# Tubes.net
KiCad netlist of a schematic drawn in EAGLE
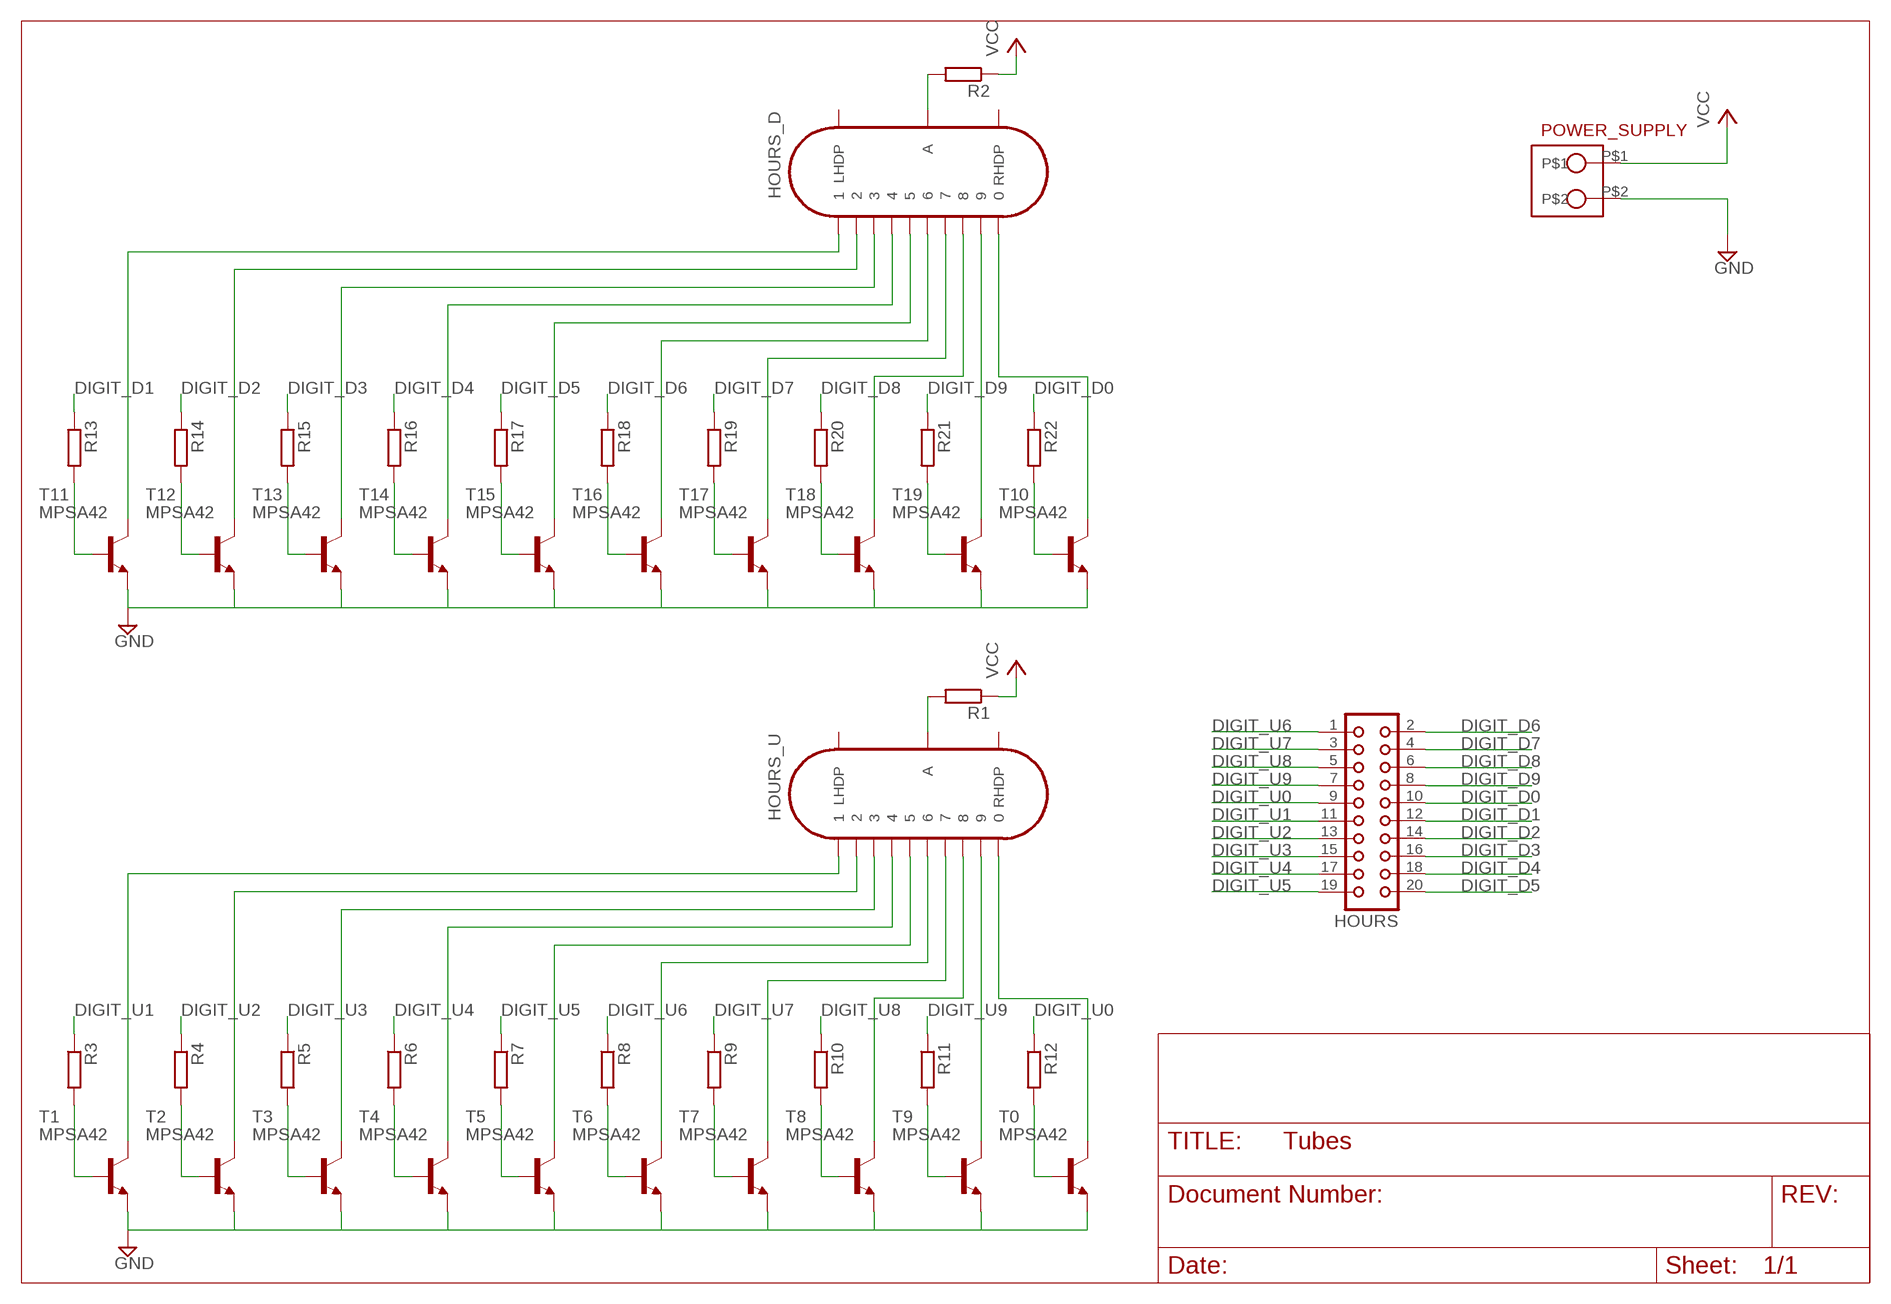
[diagram p0: schematic, sheet 1]

(export (version "E")
  (design (tool "Eeschema 10.0.6"))
  (components
    (comp (ref "HOURS")
      (value "CON20")
      (footprint "eagle-import:CON20")
      (libsource (lib "eagle-import") (part "CON20"))
    )
    (comp (ref "HOURS_D")
      (value "IN-14")
      (footprint "eagle-import:IN-14")
      (libsource (lib "eagle-import") (part "IN-14"))
    )
    (comp (ref "HOURS_U")
      (value "IN-14")
      (footprint "eagle-import:IN-14")
      (libsource (lib "eagle-import") (part "IN-14"))
    )
    (comp (ref "POWER_SUPPLY")
      (value "CON_2_SIL")
      (footprint "eagle-import:SIL_2_0.2INCH")
      (libsource (lib "eagle-import") (part "CON_2_SIL"))
    )
    (comp (ref "R1")
      (value "R-EU_0207/10")
      (footprint "eagle-import:0207_10")
      (libsource (lib "eagle-import") (part "R-EU_0207/10"))
    )
    (comp (ref "R2")
      (value "R-EU_0207/10")
      (footprint "eagle-import:0207_10")
      (libsource (lib "eagle-import") (part "R-EU_0207/10"))
    )
    (comp (ref "R3")
      (value "R-EU_0207/10")
      (footprint "eagle-import:0207_10")
      (libsource (lib "eagle-import") (part "R-EU_0207/10"))
    )
    (comp (ref "R4")
      (value "R-EU_0207/10")
      (footprint "eagle-import:0207_10")
      (libsource (lib "eagle-import") (part "R-EU_0207/10"))
    )
    (comp (ref "R5")
      (value "R-EU_0207/10")
      (footprint "eagle-import:0207_10")
      (libsource (lib "eagle-import") (part "R-EU_0207/10"))
    )
    (comp (ref "R6")
      (value "R-EU_0207/10")
      (footprint "eagle-import:0207_10")
      (libsource (lib "eagle-import") (part "R-EU_0207/10"))
    )
    (comp (ref "R7")
      (value "R-EU_0207/10")
      (footprint "eagle-import:0207_10")
      (libsource (lib "eagle-import") (part "R-EU_0207/10"))
    )
    (comp (ref "R8")
      (value "R-EU_0207/10")
      (footprint "eagle-import:0207_10")
      (libsource (lib "eagle-import") (part "R-EU_0207/10"))
    )
    (comp (ref "R9")
      (value "R-EU_0207/10")
      (footprint "eagle-import:0207_10")
      (libsource (lib "eagle-import") (part "R-EU_0207/10"))
    )
    (comp (ref "R10")
      (value "R-EU_0207/10")
      (footprint "eagle-import:0207_10")
      (libsource (lib "eagle-import") (part "R-EU_0207/10"))
    )
    (comp (ref "R11")
      (value "R-EU_0207/10")
      (footprint "eagle-import:0207_10")
      (libsource (lib "eagle-import") (part "R-EU_0207/10"))
    )
    (comp (ref "R12")
      (value "R-EU_0207/10")
      (footprint "eagle-import:0207_10")
      (libsource (lib "eagle-import") (part "R-EU_0207/10"))
    )
    (comp (ref "R13")
      (value "R-EU_0207/10")
      (footprint "eagle-import:0207_10")
      (libsource (lib "eagle-import") (part "R-EU_0207/10"))
    )
    (comp (ref "R14")
      (value "R-EU_0207/10")
      (footprint "eagle-import:0207_10")
      (libsource (lib "eagle-import") (part "R-EU_0207/10"))
    )
    (comp (ref "R15")
      (value "R-EU_0207/10")
      (footprint "eagle-import:0207_10")
      (libsource (lib "eagle-import") (part "R-EU_0207/10"))
    )
    (comp (ref "R16")
      (value "R-EU_0207/10")
      (footprint "eagle-import:0207_10")
      (libsource (lib "eagle-import") (part "R-EU_0207/10"))
    )
    (comp (ref "R17")
      (value "R-EU_0207/10")
      (footprint "eagle-import:0207_10")
      (libsource (lib "eagle-import") (part "R-EU_0207/10"))
    )
    (comp (ref "R18")
      (value "R-EU_0207/10")
      (footprint "eagle-import:0207_10")
      (libsource (lib "eagle-import") (part "R-EU_0207/10"))
    )
    (comp (ref "R19")
      (value "R-EU_0207/10")
      (footprint "eagle-import:0207_10")
      (libsource (lib "eagle-import") (part "R-EU_0207/10"))
    )
    (comp (ref "R20")
      (value "R-EU_0207/10")
      (footprint "eagle-import:0207_10")
      (libsource (lib "eagle-import") (part "R-EU_0207/10"))
    )
    (comp (ref "R21")
      (value "R-EU_0207/10")
      (footprint "eagle-import:0207_10")
      (libsource (lib "eagle-import") (part "R-EU_0207/10"))
    )
    (comp (ref "R22")
      (value "R-EU_0207/10")
      (footprint "eagle-import:0207_10")
      (libsource (lib "eagle-import") (part "R-EU_0207/10"))
    )
    (comp (ref "T0")
      (value "MPSA42")
      (footprint "eagle-import:TO92")
      (libsource (lib "eagle-import") (part "MPSA42"))
    )
    (comp (ref "T1")
      (value "MPSA42")
      (footprint "eagle-import:TO92")
      (libsource (lib "eagle-import") (part "MPSA42"))
    )
    (comp (ref "T2")
      (value "MPSA42")
      (footprint "eagle-import:TO92")
      (libsource (lib "eagle-import") (part "MPSA42"))
    )
    (comp (ref "T3")
      (value "MPSA42")
      (footprint "eagle-import:TO92")
      (libsource (lib "eagle-import") (part "MPSA42"))
    )
    (comp (ref "T4")
      (value "MPSA42")
      (footprint "eagle-import:TO92")
      (libsource (lib "eagle-import") (part "MPSA42"))
    )
    (comp (ref "T5")
      (value "MPSA42")
      (footprint "eagle-import:TO92")
      (libsource (lib "eagle-import") (part "MPSA42"))
    )
    (comp (ref "T6")
      (value "MPSA42")
      (footprint "eagle-import:TO92")
      (libsource (lib "eagle-import") (part "MPSA42"))
    )
    (comp (ref "T7")
      (value "MPSA42")
      (footprint "eagle-import:TO92")
      (libsource (lib "eagle-import") (part "MPSA42"))
    )
    (comp (ref "T8")
      (value "MPSA42")
      (footprint "eagle-import:TO92")
      (libsource (lib "eagle-import") (part "MPSA42"))
    )
    (comp (ref "T9")
      (value "MPSA42")
      (footprint "eagle-import:TO92")
      (libsource (lib "eagle-import") (part "MPSA42"))
    )
    (comp (ref "T10")
      (value "MPSA42")
      (footprint "eagle-import:TO92")
      (libsource (lib "eagle-import") (part "MPSA42"))
    )
    (comp (ref "T11")
      (value "MPSA42")
      (footprint "eagle-import:TO92")
      (libsource (lib "eagle-import") (part "MPSA42"))
    )
    (comp (ref "T12")
      (value "MPSA42")
      (footprint "eagle-import:TO92")
      (libsource (lib "eagle-import") (part "MPSA42"))
    )
    (comp (ref "T13")
      (value "MPSA42")
      (footprint "eagle-import:TO92")
      (libsource (lib "eagle-import") (part "MPSA42"))
    )
    (comp (ref "T14")
      (value "MPSA42")
      (footprint "eagle-import:TO92")
      (libsource (lib "eagle-import") (part "MPSA42"))
    )
    (comp (ref "T15")
      (value "MPSA42")
      (footprint "eagle-import:TO92")
      (libsource (lib "eagle-import") (part "MPSA42"))
    )
    (comp (ref "T16")
      (value "MPSA42")
      (footprint "eagle-import:TO92")
      (libsource (lib "eagle-import") (part "MPSA42"))
    )
    (comp (ref "T17")
      (value "MPSA42")
      (footprint "eagle-import:TO92")
      (libsource (lib "eagle-import") (part "MPSA42"))
    )
    (comp (ref "T18")
      (value "MPSA42")
      (footprint "eagle-import:TO92")
      (libsource (lib "eagle-import") (part "MPSA42"))
    )
    (comp (ref "T19")
      (value "MPSA42")
      (footprint "eagle-import:TO92")
      (libsource (lib "eagle-import") (part "MPSA42"))
    )
  )
  (nets
    (net (code "1") (name "/DIGIT_D0") (class "Default")
      (node (ref "HOURS") (pin "10") (pinfunction "10_10") (pintype "passive"))
      (node (ref "R22") (pin "1") (pinfunction "1_1") (pintype "passive"))
    )
    (net (code "2") (name "/DIGIT_D1") (class "Default")
      (node (ref "HOURS") (pin "12") (pinfunction "12_12") (pintype "passive"))
      (node (ref "R13") (pin "1") (pinfunction "1_1") (pintype "passive"))
    )
    (net (code "3") (name "/DIGIT_D2") (class "Default")
      (node (ref "HOURS") (pin "14") (pinfunction "14_14") (pintype "passive"))
      (node (ref "R14") (pin "1") (pinfunction "1_1") (pintype "passive"))
    )
    (net (code "4") (name "/DIGIT_D3") (class "Default")
      (node (ref "HOURS") (pin "16") (pinfunction "16_16") (pintype "passive"))
      (node (ref "R15") (pin "1") (pinfunction "1_1") (pintype "passive"))
    )
    (net (code "5") (name "/DIGIT_D4") (class "Default")
      (node (ref "HOURS") (pin "18") (pinfunction "18_18") (pintype "passive"))
      (node (ref "R16") (pin "1") (pinfunction "1_1") (pintype "passive"))
    )
    (net (code "6") (name "/DIGIT_D5") (class "Default")
      (node (ref "HOURS") (pin "20") (pinfunction "20_20") (pintype "passive"))
      (node (ref "R17") (pin "1") (pinfunction "1_1") (pintype "passive"))
    )
    (net (code "7") (name "/DIGIT_D6") (class "Default")
      (node (ref "HOURS") (pin "2") (pinfunction "2_2") (pintype "passive"))
      (node (ref "R18") (pin "1") (pinfunction "1_1") (pintype "passive"))
    )
    (net (code "8") (name "/DIGIT_D7") (class "Default")
      (node (ref "HOURS") (pin "4") (pinfunction "4_4") (pintype "passive"))
      (node (ref "R19") (pin "1") (pinfunction "1_1") (pintype "passive"))
    )
    (net (code "9") (name "/DIGIT_D8") (class "Default")
      (node (ref "HOURS") (pin "6") (pinfunction "6_6") (pintype "passive"))
      (node (ref "R20") (pin "1") (pinfunction "1_1") (pintype "passive"))
    )
    (net (code "10") (name "/DIGIT_D9") (class "Default")
      (node (ref "HOURS") (pin "8") (pinfunction "8_8") (pintype "passive"))
      (node (ref "R21") (pin "1") (pinfunction "1_1") (pintype "passive"))
    )
    (net (code "11") (name "/DIGIT_U0") (class "Default")
      (node (ref "HOURS") (pin "9") (pinfunction "9_9") (pintype "passive"))
      (node (ref "R12") (pin "1") (pinfunction "1_1") (pintype "passive"))
    )
    (net (code "12") (name "/DIGIT_U1") (class "Default")
      (node (ref "HOURS") (pin "11") (pinfunction "11_11") (pintype "passive"))
      (node (ref "R3") (pin "1") (pinfunction "1_1") (pintype "passive"))
    )
    (net (code "13") (name "/DIGIT_U2") (class "Default")
      (node (ref "HOURS") (pin "13") (pinfunction "13_13") (pintype "passive"))
      (node (ref "R4") (pin "1") (pinfunction "1_1") (pintype "passive"))
    )
    (net (code "14") (name "/DIGIT_U3") (class "Default")
      (node (ref "HOURS") (pin "15") (pinfunction "15_15") (pintype "passive"))
      (node (ref "R5") (pin "1") (pinfunction "1_1") (pintype "passive"))
    )
    (net (code "15") (name "/DIGIT_U4") (class "Default")
      (node (ref "HOURS") (pin "17") (pinfunction "17_17") (pintype "passive"))
      (node (ref "R6") (pin "1") (pinfunction "1_1") (pintype "passive"))
    )
    (net (code "16") (name "/DIGIT_U5") (class "Default")
      (node (ref "HOURS") (pin "19") (pinfunction "19_19") (pintype "passive"))
      (node (ref "R7") (pin "1") (pinfunction "1_1") (pintype "passive"))
    )
    (net (code "17") (name "/DIGIT_U6") (class "Default")
      (node (ref "HOURS") (pin "1") (pinfunction "1_1") (pintype "passive"))
      (node (ref "R8") (pin "1") (pinfunction "1_1") (pintype "passive"))
    )
    (net (code "18") (name "/DIGIT_U7") (class "Default")
      (node (ref "HOURS") (pin "3") (pinfunction "3_3") (pintype "passive"))
      (node (ref "R9") (pin "1") (pinfunction "1_1") (pintype "passive"))
    )
    (net (code "19") (name "/DIGIT_U8") (class "Default")
      (node (ref "HOURS") (pin "5") (pinfunction "5_5") (pintype "passive"))
      (node (ref "R10") (pin "1") (pinfunction "1_1") (pintype "passive"))
    )
    (net (code "20") (name "/DIGIT_U9") (class "Default")
      (node (ref "HOURS") (pin "7") (pinfunction "7_7") (pintype "passive"))
      (node (ref "R11") (pin "1") (pinfunction "1_1") (pintype "passive"))
    )
    (net (code "21") (name "GND") (class "Default")
      (node (ref "POWER_SUPPLY") (pin "P$2") (pinfunction "P$2_P$2") (pintype "bidirectional"))
      (node (ref "T0") (pin "1") (pinfunction "E_1") (pintype "passive"))
      (node (ref "T1") (pin "1") (pinfunction "E_1") (pintype "passive"))
      (node (ref "T10") (pin "1") (pinfunction "E_1") (pintype "passive"))
      (node (ref "T11") (pin "1") (pinfunction "E_1") (pintype "passive"))
      (node (ref "T12") (pin "1") (pinfunction "E_1") (pintype "passive"))
      (node (ref "T13") (pin "1") (pinfunction "E_1") (pintype "passive"))
      (node (ref "T14") (pin "1") (pinfunction "E_1") (pintype "passive"))
      (node (ref "T15") (pin "1") (pinfunction "E_1") (pintype "passive"))
      (node (ref "T16") (pin "1") (pinfunction "E_1") (pintype "passive"))
      (node (ref "T17") (pin "1") (pinfunction "E_1") (pintype "passive"))
      (node (ref "T18") (pin "1") (pinfunction "E_1") (pintype "passive"))
      (node (ref "T19") (pin "1") (pinfunction "E_1") (pintype "passive"))
      (node (ref "T2") (pin "1") (pinfunction "E_1") (pintype "passive"))
      (node (ref "T3") (pin "1") (pinfunction "E_1") (pintype "passive"))
      (node (ref "T4") (pin "1") (pinfunction "E_1") (pintype "passive"))
      (node (ref "T5") (pin "1") (pinfunction "E_1") (pintype "passive"))
      (node (ref "T6") (pin "1") (pinfunction "E_1") (pintype "passive"))
      (node (ref "T7") (pin "1") (pinfunction "E_1") (pintype "passive"))
      (node (ref "T8") (pin "1") (pinfunction "E_1") (pintype "passive"))
      (node (ref "T9") (pin "1") (pinfunction "E_1") (pintype "passive"))
    )
    (net (code "22") (name "Net-(HOURS_D-PadA)") (class "Default")
      (node (ref "HOURS_D") (pin "A") (pinfunction "A_A") (pintype "bidirectional"))
      (node (ref "R2") (pin "2") (pinfunction "2_2") (pintype "passive"))
    )
    (net (code "23") (name "Net-(HOURS_U-PadA)") (class "Default")
      (node (ref "HOURS_U") (pin "A") (pinfunction "A_A") (pintype "bidirectional"))
      (node (ref "R1") (pin "2") (pinfunction "2_2") (pintype "passive"))
    )
    (net (code "24") (name "Net-(T0-B)") (class "Default")
      (node (ref "R12") (pin "2") (pinfunction "2_2") (pintype "passive"))
      (node (ref "T0") (pin "2") (pinfunction "B_2") (pintype "passive"))
    )
    (net (code "25") (name "Net-(T0-C)") (class "Default")
      (node (ref "HOURS_U") (pin "0") (pinfunction "0_0") (pintype "bidirectional"))
      (node (ref "T0") (pin "3") (pinfunction "C_3") (pintype "passive"))
    )
    (net (code "26") (name "Net-(T1-B)") (class "Default")
      (node (ref "R3") (pin "2") (pinfunction "2_2") (pintype "passive"))
      (node (ref "T1") (pin "2") (pinfunction "B_2") (pintype "passive"))
    )
    (net (code "27") (name "Net-(T1-C)") (class "Default")
      (node (ref "HOURS_U") (pin "1") (pinfunction "1_1") (pintype "bidirectional"))
      (node (ref "T1") (pin "3") (pinfunction "C_3") (pintype "passive"))
    )
    (net (code "28") (name "Net-(T2-B)") (class "Default")
      (node (ref "R4") (pin "2") (pinfunction "2_2") (pintype "passive"))
      (node (ref "T2") (pin "2") (pinfunction "B_2") (pintype "passive"))
    )
    (net (code "29") (name "Net-(T2-C)") (class "Default")
      (node (ref "HOURS_U") (pin "2") (pinfunction "2_2") (pintype "bidirectional"))
      (node (ref "T2") (pin "3") (pinfunction "C_3") (pintype "passive"))
    )
    (net (code "30") (name "Net-(T3-B)") (class "Default")
      (node (ref "R5") (pin "2") (pinfunction "2_2") (pintype "passive"))
      (node (ref "T3") (pin "2") (pinfunction "B_2") (pintype "passive"))
    )
    (net (code "31") (name "Net-(T3-C)") (class "Default")
      (node (ref "HOURS_U") (pin "3") (pinfunction "3_3") (pintype "bidirectional"))
      (node (ref "T3") (pin "3") (pinfunction "C_3") (pintype "passive"))
    )
    (net (code "32") (name "Net-(T4-B)") (class "Default")
      (node (ref "R6") (pin "2") (pinfunction "2_2") (pintype "passive"))
      (node (ref "T4") (pin "2") (pinfunction "B_2") (pintype "passive"))
    )
    (net (code "33") (name "Net-(T4-C)") (class "Default")
      (node (ref "HOURS_U") (pin "4") (pinfunction "4_4") (pintype "bidirectional"))
      (node (ref "T4") (pin "3") (pinfunction "C_3") (pintype "passive"))
    )
    (net (code "34") (name "Net-(T5-B)") (class "Default")
      (node (ref "R7") (pin "2") (pinfunction "2_2") (pintype "passive"))
      (node (ref "T5") (pin "2") (pinfunction "B_2") (pintype "passive"))
    )
    (net (code "35") (name "Net-(T5-C)") (class "Default")
      (node (ref "HOURS_U") (pin "5") (pinfunction "5_5") (pintype "bidirectional"))
      (node (ref "T5") (pin "3") (pinfunction "C_3") (pintype "passive"))
    )
    (net (code "36") (name "Net-(T6-B)") (class "Default")
      (node (ref "R8") (pin "2") (pinfunction "2_2") (pintype "passive"))
      (node (ref "T6") (pin "2") (pinfunction "B_2") (pintype "passive"))
    )
    (net (code "37") (name "Net-(T6-C)") (class "Default")
      (node (ref "HOURS_U") (pin "6") (pinfunction "6_6") (pintype "bidirectional"))
      (node (ref "T6") (pin "3") (pinfunction "C_3") (pintype "passive"))
    )
    (net (code "38") (name "Net-(T7-B)") (class "Default")
      (node (ref "R9") (pin "2") (pinfunction "2_2") (pintype "passive"))
      (node (ref "T7") (pin "2") (pinfunction "B_2") (pintype "passive"))
    )
    (net (code "39") (name "Net-(T7-C)") (class "Default")
      (node (ref "HOURS_U") (pin "7") (pinfunction "7_7") (pintype "bidirectional"))
      (node (ref "T7") (pin "3") (pinfunction "C_3") (pintype "passive"))
    )
    (net (code "40") (name "Net-(T8-B)") (class "Default")
      (node (ref "R10") (pin "2") (pinfunction "2_2") (pintype "passive"))
      (node (ref "T8") (pin "2") (pinfunction "B_2") (pintype "passive"))
    )
    (net (code "41") (name "Net-(T8-C)") (class "Default")
      (node (ref "HOURS_U") (pin "8") (pinfunction "8_8") (pintype "bidirectional"))
      (node (ref "T8") (pin "3") (pinfunction "C_3") (pintype "passive"))
    )
    (net (code "42") (name "Net-(T9-B)") (class "Default")
      (node (ref "R11") (pin "2") (pinfunction "2_2") (pintype "passive"))
      (node (ref "T9") (pin "2") (pinfunction "B_2") (pintype "passive"))
    )
    (net (code "43") (name "Net-(T9-C)") (class "Default")
      (node (ref "HOURS_U") (pin "9") (pinfunction "9_9") (pintype "bidirectional"))
      (node (ref "T9") (pin "3") (pinfunction "C_3") (pintype "passive"))
    )
    (net (code "44") (name "Net-(T10-B)") (class "Default")
      (node (ref "R22") (pin "2") (pinfunction "2_2") (pintype "passive"))
      (node (ref "T10") (pin "2") (pinfunction "B_2") (pintype "passive"))
    )
    (net (code "45") (name "Net-(T10-C)") (class "Default")
      (node (ref "HOURS_D") (pin "0") (pinfunction "0_0") (pintype "bidirectional"))
      (node (ref "T10") (pin "3") (pinfunction "C_3") (pintype "passive"))
    )
    (net (code "46") (name "Net-(T11-B)") (class "Default")
      (node (ref "R13") (pin "2") (pinfunction "2_2") (pintype "passive"))
      (node (ref "T11") (pin "2") (pinfunction "B_2") (pintype "passive"))
    )
    (net (code "47") (name "Net-(T11-C)") (class "Default")
      (node (ref "HOURS_D") (pin "1") (pinfunction "1_1") (pintype "bidirectional"))
      (node (ref "T11") (pin "3") (pinfunction "C_3") (pintype "passive"))
    )
    (net (code "48") (name "Net-(T12-B)") (class "Default")
      (node (ref "R14") (pin "2") (pinfunction "2_2") (pintype "passive"))
      (node (ref "T12") (pin "2") (pinfunction "B_2") (pintype "passive"))
    )
    (net (code "49") (name "Net-(T12-C)") (class "Default")
      (node (ref "HOURS_D") (pin "2") (pinfunction "2_2") (pintype "bidirectional"))
      (node (ref "T12") (pin "3") (pinfunction "C_3") (pintype "passive"))
    )
    (net (code "50") (name "Net-(T13-B)") (class "Default")
      (node (ref "R15") (pin "2") (pinfunction "2_2") (pintype "passive"))
      (node (ref "T13") (pin "2") (pinfunction "B_2") (pintype "passive"))
    )
    (net (code "51") (name "Net-(T13-C)") (class "Default")
      (node (ref "HOURS_D") (pin "3") (pinfunction "3_3") (pintype "bidirectional"))
      (node (ref "T13") (pin "3") (pinfunction "C_3") (pintype "passive"))
    )
    (net (code "52") (name "Net-(T14-B)") (class "Default")
      (node (ref "R16") (pin "2") (pinfunction "2_2") (pintype "passive"))
      (node (ref "T14") (pin "2") (pinfunction "B_2") (pintype "passive"))
    )
    (net (code "53") (name "Net-(T14-C)") (class "Default")
      (node (ref "HOURS_D") (pin "4") (pinfunction "4_4") (pintype "bidirectional"))
      (node (ref "T14") (pin "3") (pinfunction "C_3") (pintype "passive"))
    )
    (net (code "54") (name "Net-(T15-B)") (class "Default")
      (node (ref "R17") (pin "2") (pinfunction "2_2") (pintype "passive"))
      (node (ref "T15") (pin "2") (pinfunction "B_2") (pintype "passive"))
    )
    (net (code "55") (name "Net-(T15-C)") (class "Default")
      (node (ref "HOURS_D") (pin "5") (pinfunction "5_5") (pintype "bidirectional"))
      (node (ref "T15") (pin "3") (pinfunction "C_3") (pintype "passive"))
    )
    (net (code "56") (name "Net-(T16-B)") (class "Default")
      (node (ref "R18") (pin "2") (pinfunction "2_2") (pintype "passive"))
      (node (ref "T16") (pin "2") (pinfunction "B_2") (pintype "passive"))
    )
    (net (code "57") (name "Net-(T16-C)") (class "Default")
      (node (ref "HOURS_D") (pin "6") (pinfunction "6_6") (pintype "bidirectional"))
      (node (ref "T16") (pin "3") (pinfunction "C_3") (pintype "passive"))
    )
    (net (code "58") (name "Net-(T17-B)") (class "Default")
      (node (ref "R19") (pin "2") (pinfunction "2_2") (pintype "passive"))
      (node (ref "T17") (pin "2") (pinfunction "B_2") (pintype "passive"))
    )
    (net (code "59") (name "Net-(T17-C)") (class "Default")
      (node (ref "HOURS_D") (pin "7") (pinfunction "7_7") (pintype "bidirectional"))
      (node (ref "T17") (pin "3") (pinfunction "C_3") (pintype "passive"))
    )
    (net (code "60") (name "Net-(T18-B)") (class "Default")
      (node (ref "R20") (pin "2") (pinfunction "2_2") (pintype "passive"))
      (node (ref "T18") (pin "2") (pinfunction "B_2") (pintype "passive"))
    )
    (net (code "61") (name "Net-(T18-C)") (class "Default")
      (node (ref "HOURS_D") (pin "8") (pinfunction "8_8") (pintype "bidirectional"))
      (node (ref "T18") (pin "3") (pinfunction "C_3") (pintype "passive"))
    )
    (net (code "62") (name "Net-(T19-B)") (class "Default")
      (node (ref "R21") (pin "2") (pinfunction "2_2") (pintype "passive"))
      (node (ref "T19") (pin "2") (pinfunction "B_2") (pintype "passive"))
    )
    (net (code "63") (name "Net-(T19-C)") (class "Default")
      (node (ref "HOURS_D") (pin "9") (pinfunction "9_9") (pintype "bidirectional"))
      (node (ref "T19") (pin "3") (pinfunction "C_3") (pintype "passive"))
    )
    (net (code "64") (name "VCC") (class "Default")
      (node (ref "POWER_SUPPLY") (pin "P$1") (pinfunction "P$1_P$1") (pintype "bidirectional"))
      (node (ref "R1") (pin "1") (pinfunction "1_1") (pintype "passive"))
      (node (ref "R2") (pin "1") (pinfunction "1_1") (pintype "passive"))
    )
    (net (code "65") (name "unconnected-(HOURS_D-PadLHDP)") (class "Default")
      (node (ref "HOURS_D") (pin "LHDP") (pinfunction "LHDP_LHDP") (pintype "bidirectional"))
    )
    (net (code "66") (name "unconnected-(HOURS_D-PadRHDP)") (class "Default")
      (node (ref "HOURS_D") (pin "RHDP") (pinfunction "RHDP_RHDP") (pintype "bidirectional"))
    )
    (net (code "67") (name "unconnected-(HOURS_U-PadLHDP)") (class "Default")
      (node (ref "HOURS_U") (pin "LHDP") (pinfunction "LHDP_LHDP") (pintype "bidirectional"))
    )
    (net (code "68") (name "unconnected-(HOURS_U-PadRHDP)") (class "Default")
      (node (ref "HOURS_U") (pin "RHDP") (pinfunction "RHDP_RHDP") (pintype "bidirectional"))
    )
  )
)
